# POWERMANAGE.net
KiCad netlist of a schematic drawn in Altium Designer
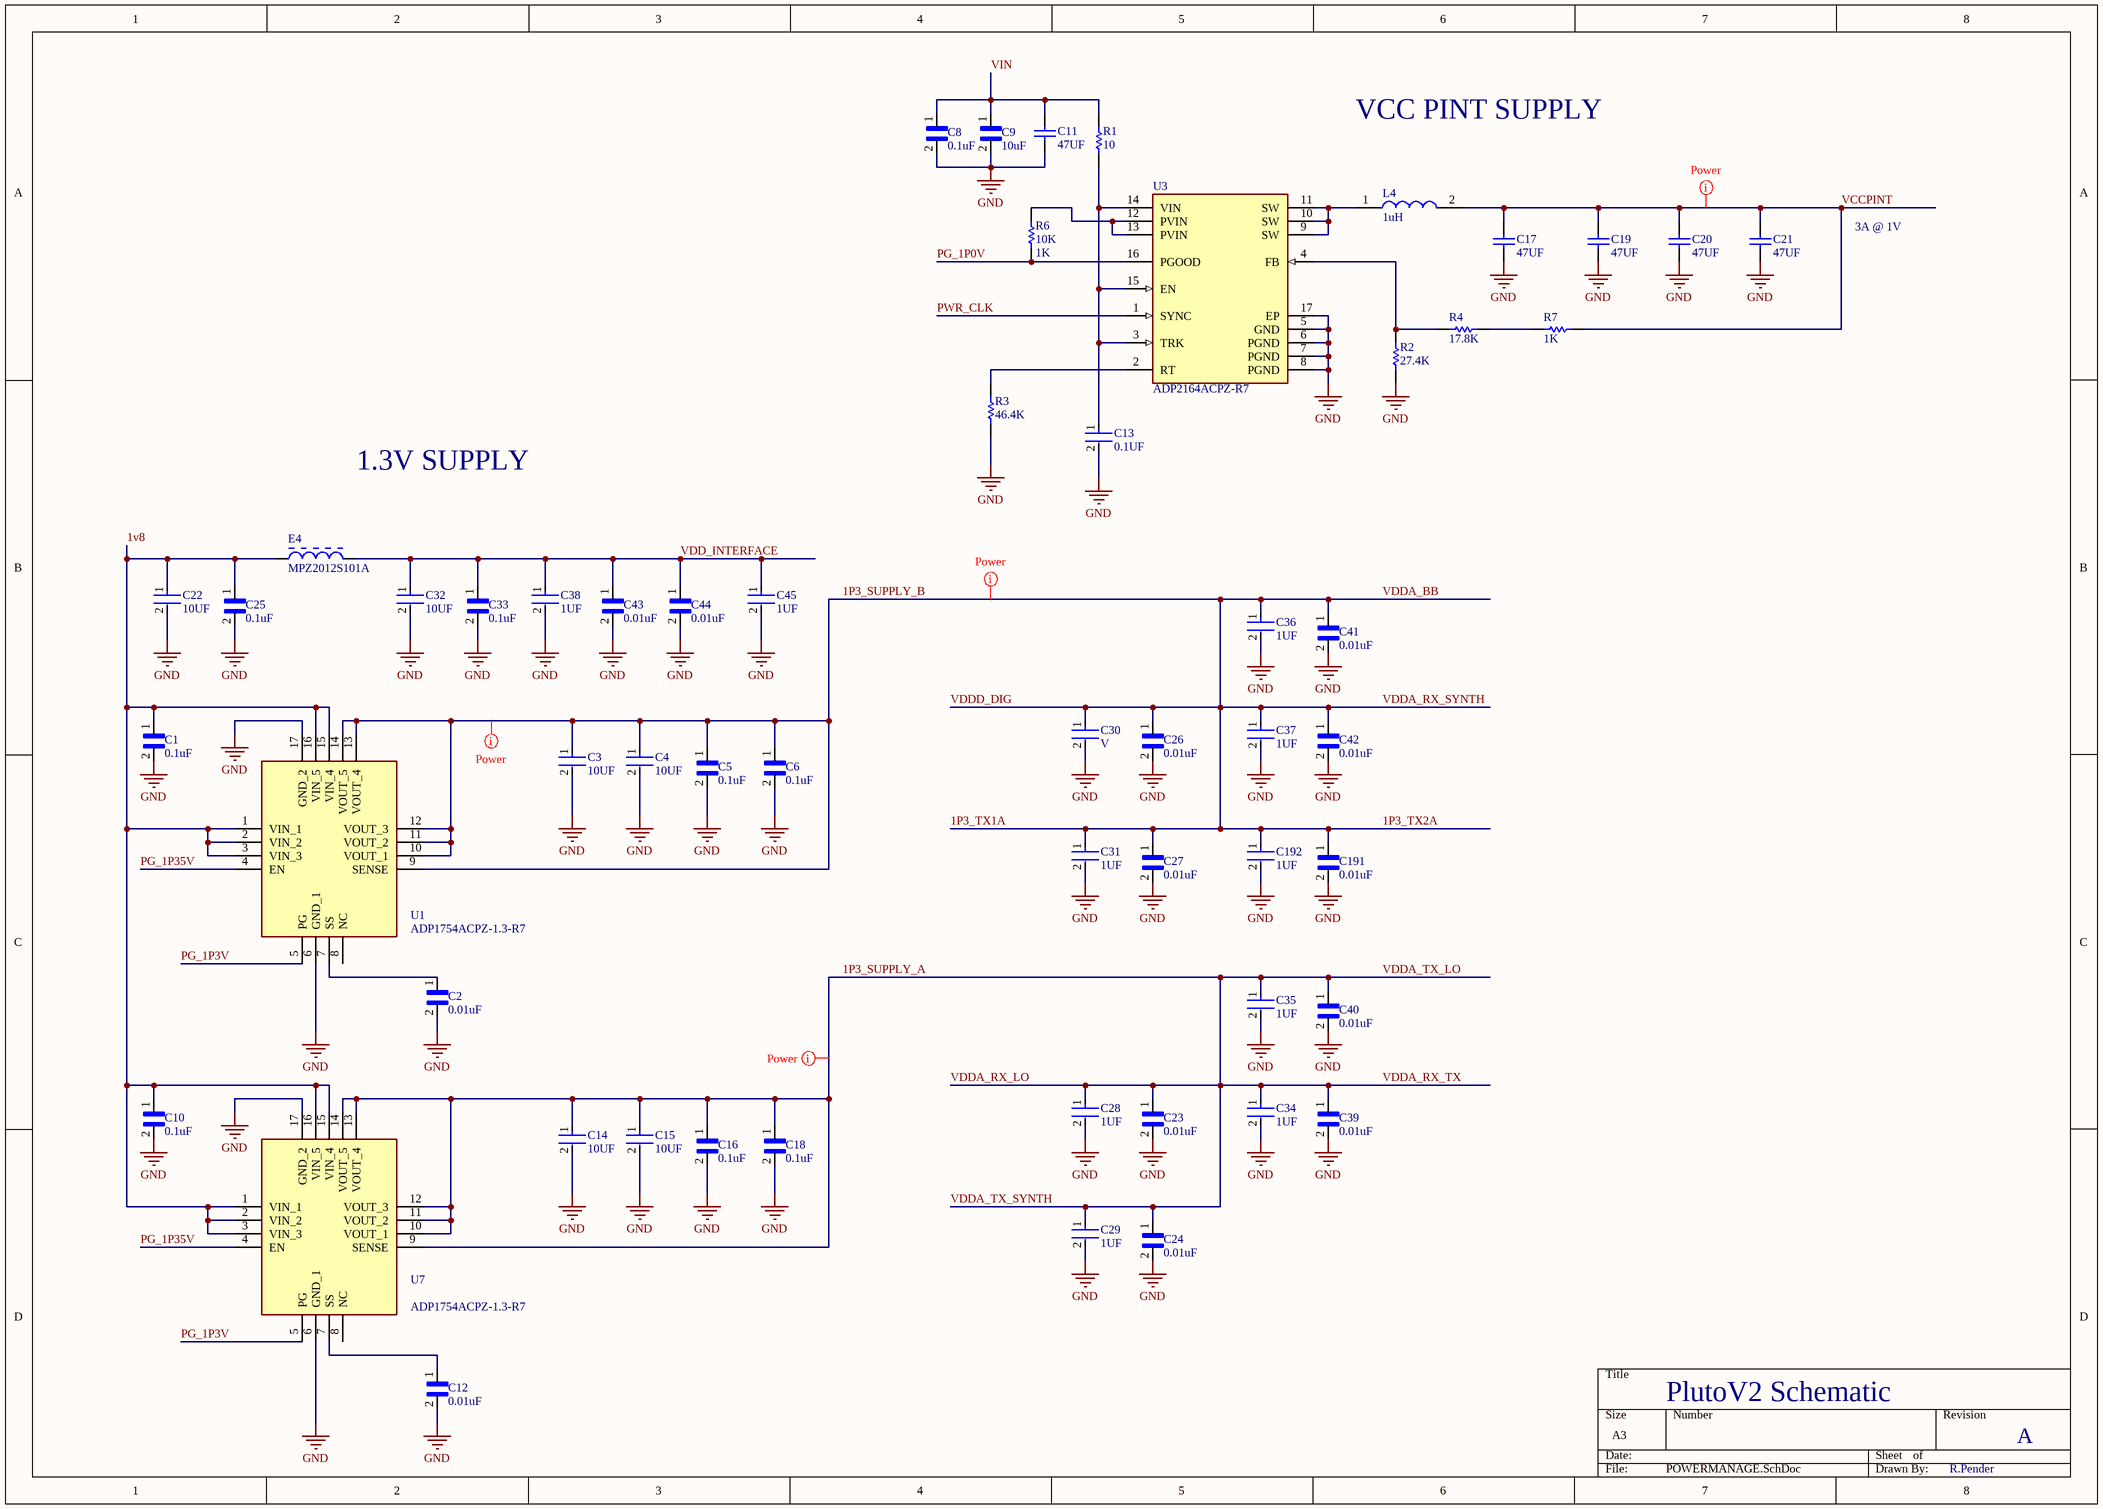
[diagram p0: POWERMANAGE.SchDoc]

(export (version "E")
  (design (tool "Eeschema 10.0.6"))
  (components
    (comp (ref "C1")
      (value "0.1uF")
      (footprint "CAPC0603X33N")
      (description "CAP 0.1UF 16VDC X5R 20% SMD 0201 PAPER TAPE")
      (fields (field (name "MP") "GRM033R61C104ME84D"))
      (libsource (lib "GRM033R61C104ME84D") (part "GRM033R61C104ME84D"))
    )
    (comp (ref "C2")
      (value "0.01uF")
      (footprint "CAPC0603X33N")
      (description "SMD Capacitor X7R(EIA) with Capacitance: 10000pF Tol. 10%. Rated Voltage: 10Vdc")
      (fields (field (name "MP") "GRM033R71A103KA01D") (field (name "MF") "Murata"))
      (libsource (lib "GRM033R71A103KA01D") (part "GRM033R71A103KA01D"))
    )
    (comp (ref "C3")
      (value "10UF")
      (footprint "FP-GRM188-0_1-e0_2_0_55-IPC_A")
      (description "Chip Multilayer Ceramic Capacitors for General Purpose, 0603, 10uF, X5R, 15%, 20%, 6.3V")
      (fields (field (name "VOLTAGE") "6.3V") (field (name "TOLERANCE") "20%"))
      (libsource (lib "Altium Content Vault") (part "02cd4be3c70576c341d710602a673aa"))
    )
    (comp (ref "C4")
      (value "10UF")
      (footprint "FP-GRM188-0_1-e0_2_0_55-IPC_A")
      (description "Chip Multilayer Ceramic Capacitors for General Purpose, 0603, 10uF, X5R, 15%, 20%, 6.3V")
      (fields (field (name "VOLTAGE") "6.3V") (field (name "TOLERANCE") "20%"))
      (libsource (lib "Altium Content Vault") (part "02cd4be3c70576c341d710602a673aa"))
    )
    (comp (ref "C5")
      (value "0.1uF")
      (footprint "CAPC0603X33N")
      (description "CAP 0.1UF 16VDC X5R 20% SMD 0201 PAPER TAPE")
      (fields (field (name "MP") "GRM033R61C104ME84D"))
      (libsource (lib "GRM033R61C104ME84D") (part "GRM033R61C104ME84D"))
    )
    (comp (ref "C6")
      (value "0.1uF")
      (footprint "CAPC0603X33N")
      (description "CAP 0.1UF 16VDC X5R 20% SMD 0201 PAPER TAPE")
      (fields (field (name "MP") "GRM033R61C104ME84D"))
      (libsource (lib "GRM033R61C104ME84D") (part "GRM033R61C104ME84D"))
    )
    (comp (ref "C8")
      (value "0.1uF")
      (footprint "CAPC0603X33N")
      (description "CAP 0.1UF 16VDC X5R 20% SMD 0201 PAPER TAPE")
      (fields (field (name "MP") "GRM033R61C104ME84D"))
      (libsource (lib "GRM033R61C104ME84D") (part "GRM033R61C104ME84D"))
    )
    (comp (ref "C9")
      (value "10uF")
      (footprint "CAPC0603X33N")
      (description "SMD Capacitor X7R(EIA) with Capacitance: 10000pF Tol. 10%. Rated Voltage: 10Vdc")
      (fields (field (name "MP") "GRM033R71A103KA01D") (field (name "MF") "Murata"))
      (libsource (lib "GRM033R71A103KA01D") (part "GRM033R71A103KA01D"))
    )
    (comp (ref "C10")
      (value "0.1uF")
      (footprint "CAPC0603X33N")
      (description "CAP 0.1UF 16VDC X5R 20% SMD 0201 PAPER TAPE")
      (fields (field (name "MP") "GRM033R61C104ME84D"))
      (libsource (lib "GRM033R61C104ME84D") (part "GRM033R61C104ME84D"))
    )
    (comp (ref "C11")
      (value "47UF")
      (footprint "TAYO-JMK212BBJ476MG-T_L")
      (fields
        (field (name "MANUFACTURER") "Taiyo Yuden")
        (field (name "TOLERANCE") "±20%")
        (field (name "PCN PART NUMBER") "X5R,X7RDielectrics23/Jan/2008")
      )
      (libsource (lib "Altium Content Vault") (part "CAP-NP-2"))
    )
    (comp (ref "C12")
      (value "0.01uF")
      (footprint "CAPC0603X33N")
      (description "SMD Capacitor X7R(EIA) with Capacitance: 10000pF Tol. 10%. Rated Voltage: 10Vdc")
      (fields (field (name "MP") "GRM033R71A103KA01D") (field (name "MF") "Murata"))
      (libsource (lib "GRM033R71A103KA01D") (part "GRM033R71A103KA01D"))
    )
    (comp (ref "C13")
      (value "0.1UF")
      (footprint "FP-GRM188-0_15-MFG")
      (description "Chip Multilayer Ceramic Capacitors for General Purpose, 0603, 10uF, X5R, 15%, 20%, 10V")
      (fields (field (name "TOLERANCE") "20%"))
      (libsource (lib "Altium Content Vault") (part "02cd4be3c70576c341d710602a673aa"))
    )
    (comp (ref "C14")
      (value "10UF")
      (footprint "FP-GRM188-0_1-e0_2_0_55-IPC_A")
      (description "Chip Multilayer Ceramic Capacitors for General Purpose, 0603, 10uF, X5R, 15%, 20%, 6.3V")
      (fields (field (name "VOLTAGE") "6.3V") (field (name "TOLERANCE") "20%"))
      (libsource (lib "Altium Content Vault") (part "02cd4be3c70576c341d710602a673aa"))
    )
    (comp (ref "C15")
      (value "10UF")
      (footprint "FP-GRM188-0_1-e0_2_0_55-IPC_A")
      (description "Chip Multilayer Ceramic Capacitors for General Purpose, 0603, 10uF, X5R, 15%, 20%, 6.3V")
      (fields (field (name "VOLTAGE") "6.3V") (field (name "TOLERANCE") "20%"))
      (libsource (lib "Altium Content Vault") (part "02cd4be3c70576c341d710602a673aa"))
    )
    (comp (ref "C16")
      (value "0.1uF")
      (footprint "CAPC0603X33N")
      (description "CAP 0.1UF 16VDC X5R 20% SMD 0201 PAPER TAPE")
      (fields (field (name "MP") "GRM033R61C104ME84D"))
      (libsource (lib "GRM033R61C104ME84D") (part "GRM033R61C104ME84D"))
    )
    (comp (ref "C17")
      (value "47UF")
      (footprint "TAYO-JMK212BBJ476MG-T_L")
      (fields
        (field (name "MANUFACTURER") "Taiyo Yuden")
        (field (name "TOLERANCE") "±20%")
        (field (name "PCN PART NUMBER") "X5R,X7RDielectrics23/Jan/2008")
      )
      (libsource (lib "Altium Content Vault") (part "CAP-NP-2"))
    )
    (comp (ref "C18")
      (value "0.1uF")
      (footprint "CAPC0603X33N")
      (description "CAP 0.1UF 16VDC X5R 20% SMD 0201 PAPER TAPE")
      (fields (field (name "MP") "GRM033R61C104ME84D"))
      (libsource (lib "GRM033R61C104ME84D") (part "GRM033R61C104ME84D"))
    )
    (comp (ref "C19")
      (value "47UF")
      (footprint "TAYO-JMK212BBJ476MG-T_L")
      (fields
        (field (name "MANUFACTURER") "Taiyo Yuden")
        (field (name "TOLERANCE") "±20%")
        (field (name "PCN PART NUMBER") "X5R,X7RDielectrics23/Jan/2008")
      )
      (libsource (lib "Altium Content Vault") (part "CAP-NP-2"))
    )
    (comp (ref "C20")
      (value "47UF")
      (footprint "TAYO-JMK212BBJ476MG-T_L")
      (fields
        (field (name "MANUFACTURER") "Taiyo Yuden")
        (field (name "TOLERANCE") "±20%")
        (field (name "PCN PART NUMBER") "X5R,X7RDielectrics23/Jan/2008")
      )
      (libsource (lib "Altium Content Vault") (part "CAP-NP-2"))
    )
    (comp (ref "C21")
      (value "47UF")
      (footprint "TAYO-JMK212BBJ476MG-T_L")
      (fields
        (field (name "MANUFACTURER") "Taiyo Yuden")
        (field (name "TOLERANCE") "±20%")
        (field (name "PCN PART NUMBER") "X5R,X7RDielectrics23/Jan/2008")
      )
      (libsource (lib "Altium Content Vault") (part "CAP-NP-2"))
    )
    (comp (ref "C22")
      (value "10UF")
      (footprint "FP-GRM188-0_1-e0_2_0_55-IPC_A")
      (description "Chip Multilayer Ceramic Capacitors for General Purpose, 0603, 10uF, X5R, 15%, 20%, 6.3V")
      (fields (field (name "VOLTAGE") "6.3V") (field (name "TOLERANCE") "20%"))
      (libsource (lib "Altium Content Vault") (part "02cd4be3c70576c341d710602a673aa"))
    )
    (comp (ref "C23")
      (value "0.01uF")
      (footprint "CAPC0603X33N")
      (description "SMD Capacitor X7R(EIA) with Capacitance: 10000pF Tol. 10%. Rated Voltage: 10Vdc")
      (fields (field (name "MP") "GRM033R71A103KA01D") (field (name "MF") "Murata"))
      (libsource (lib "GRM033R71A103KA01D") (part "GRM033R71A103KA01D"))
    )
    (comp (ref "C24")
      (value "0.01uF")
      (footprint "CAPC0603X33N")
      (description "SMD Capacitor X7R(EIA) with Capacitance: 10000pF Tol. 10%. Rated Voltage: 10Vdc")
      (fields (field (name "MP") "GRM033R71A103KA01D") (field (name "MF") "Murata"))
      (libsource (lib "GRM033R71A103KA01D") (part "GRM033R71A103KA01D"))
    )
    (comp (ref "C25")
      (value "0.1uF")
      (footprint "CAPC0603X33N")
      (description "CAP 0.1UF 16VDC X5R 20% SMD 0201 PAPER TAPE")
      (fields (field (name "MP") "GRM033R61C104ME84D"))
      (libsource (lib "GRM033R61C104ME84D") (part "GRM033R61C104ME84D"))
    )
    (comp (ref "C26")
      (value "0.01uF")
      (footprint "CAPC0603X33N")
      (description "SMD Capacitor X7R(EIA) with Capacitance: 10000pF Tol. 10%. Rated Voltage: 10Vdc")
      (fields (field (name "MP") "GRM033R71A103KA01D") (field (name "MF") "Murata"))
      (libsource (lib "GRM033R71A103KA01D") (part "GRM033R71A103KA01D"))
    )
    (comp (ref "C27")
      (value "0.01uF")
      (footprint "CAPC0603X33N")
      (description "SMD Capacitor X7R(EIA) with Capacitance: 10000pF Tol. 10%. Rated Voltage: 10Vdc")
      (fields (field (name "MP") "GRM033R71A103KA01D") (field (name "MF") "Murata"))
      (libsource (lib "GRM033R71A103KA01D") (part "GRM033R71A103KA01D"))
    )
    (comp (ref "C28")
      (value "1UF")
      (footprint "FP-0402-L_1_0_0_05-W_0_5-IPC_A")
      (description "None")
      (fields (field (name "TOLERANCE") "10%"))
      (libsource (lib "Altium Content Vault") (part "b4654b650e69147ec39a6b967a45e02"))
    )
    (comp (ref "C29")
      (value "1UF")
      (footprint "FP-0402-L_1_0_0_05-W_0_5-IPC_A")
      (description "None")
      (fields (field (name "TOLERANCE") "10%"))
      (libsource (lib "Altium Content Vault") (part "b4654b650e69147ec39a6b967a45e02"))
    )
    (comp (ref "C30")
      (value "V")
      (footprint "FP-0402-L_1_0_0_05-W_0_5-IPC_A")
      (description "None")
      (fields (field (name "TOLERANCE") "10%"))
      (libsource (lib "Altium Content Vault") (part "b4654b650e69147ec39a6b967a45e02"))
    )
    (comp (ref "C31")
      (value "1UF")
      (footprint "FP-0402-L_1_0_0_05-W_0_5-IPC_A")
      (description "None")
      (fields (field (name "TOLERANCE") "10%"))
      (libsource (lib "Altium Content Vault") (part "b4654b650e69147ec39a6b967a45e02"))
    )
    (comp (ref "C32")
      (value "10UF")
      (footprint "FP-GRM188-0_1-e0_2_0_55-IPC_A")
      (description "Chip Multilayer Ceramic Capacitors for General Purpose, 0603, 10uF, X5R, 15%, 20%, 6.3V")
      (fields (field (name "VOLTAGE") "6.3V") (field (name "TOLERANCE") "20%"))
      (libsource (lib "Altium Content Vault") (part "02cd4be3c70576c341d710602a673aa"))
    )
    (comp (ref "C33")
      (value "0.1uF")
      (footprint "CAPC0603X33N")
      (description "CAP 0.1UF 16VDC X5R 20% SMD 0201 PAPER TAPE")
      (fields (field (name "MP") "GRM033R61C104ME84D"))
      (libsource (lib "GRM033R61C104ME84D") (part "GRM033R61C104ME84D"))
    )
    (comp (ref "C34")
      (value "1UF")
      (footprint "FP-0402-L_1_0_0_05-W_0_5-IPC_A")
      (description "None")
      (fields (field (name "TOLERANCE") "10%"))
      (libsource (lib "Altium Content Vault") (part "b4654b650e69147ec39a6b967a45e02"))
    )
    (comp (ref "C35")
      (value "1UF")
      (footprint "FP-0402-L_1_0_0_05-W_0_5-IPC_A")
      (description "None")
      (fields (field (name "TOLERANCE") "10%"))
      (libsource (lib "Altium Content Vault") (part "b4654b650e69147ec39a6b967a45e02"))
    )
    (comp (ref "C36")
      (value "1UF")
      (footprint "FP-0402-L_1_0_0_05-W_0_5-IPC_A")
      (description "None")
      (fields (field (name "TOLERANCE") "10%"))
      (libsource (lib "Altium Content Vault") (part "b4654b650e69147ec39a6b967a45e02"))
    )
    (comp (ref "C37")
      (value "1UF")
      (footprint "FP-0402-L_1_0_0_05-W_0_5-IPC_A")
      (description "None")
      (fields (field (name "TOLERANCE") "10%"))
      (libsource (lib "Altium Content Vault") (part "b4654b650e69147ec39a6b967a45e02"))
    )
    (comp (ref "C38")
      (value "1UF")
      (footprint "FP-0402-L_1_0_0_05-W_0_5-IPC_A")
      (description "None")
      (fields (field (name "TOLERANCE") "10%"))
      (libsource (lib "Altium Content Vault") (part "b4654b650e69147ec39a6b967a45e02"))
    )
    (comp (ref "C39")
      (value "0.01uF")
      (footprint "CAPC0603X33N")
      (description "SMD Capacitor X7R(EIA) with Capacitance: 10000pF Tol. 10%. Rated Voltage: 10Vdc")
      (fields (field (name "MP") "GRM033R71A103KA01D") (field (name "MF") "Murata"))
      (libsource (lib "GRM033R71A103KA01D") (part "GRM033R71A103KA01D"))
    )
    (comp (ref "C40")
      (value "0.01uF")
      (footprint "CAPC0603X33N")
      (description "SMD Capacitor X7R(EIA) with Capacitance: 10000pF Tol. 10%. Rated Voltage: 10Vdc")
      (fields (field (name "MP") "GRM033R71A103KA01D") (field (name "MF") "Murata"))
      (libsource (lib "GRM033R71A103KA01D") (part "GRM033R71A103KA01D"))
    )
    (comp (ref "C41")
      (value "0.01uF")
      (footprint "CAPC0603X33N")
      (description "SMD Capacitor X7R(EIA) with Capacitance: 10000pF Tol. 10%. Rated Voltage: 10Vdc")
      (fields (field (name "MP") "GRM033R71A103KA01D") (field (name "MF") "Murata"))
      (libsource (lib "GRM033R71A103KA01D") (part "GRM033R71A103KA01D"))
    )
    (comp (ref "C42")
      (value "0.01uF")
      (footprint "CAPC0603X33N")
      (description "SMD Capacitor X7R(EIA) with Capacitance: 10000pF Tol. 10%. Rated Voltage: 10Vdc")
      (fields (field (name "MP") "GRM033R71A103KA01D") (field (name "MF") "Murata"))
      (libsource (lib "GRM033R71A103KA01D") (part "GRM033R71A103KA01D"))
    )
    (comp (ref "C43")
      (value "0.01uF")
      (footprint "CAPC0603X33N")
      (description "SMD Capacitor X7R(EIA) with Capacitance: 10000pF Tol. 10%. Rated Voltage: 10Vdc")
      (fields (field (name "MP") "GRM033R71A103KA01D") (field (name "MF") "Murata"))
      (libsource (lib "GRM033R71A103KA01D") (part "GRM033R71A103KA01D"))
    )
    (comp (ref "C44")
      (value "0.01uF")
      (footprint "CAPC0603X33N")
      (description "SMD Capacitor X7R(EIA) with Capacitance: 10000pF Tol. 10%. Rated Voltage: 10Vdc")
      (fields (field (name "MP") "GRM033R71A103KA01D") (field (name "MF") "Murata"))
      (libsource (lib "GRM033R71A103KA01D") (part "GRM033R71A103KA01D"))
    )
    (comp (ref "C45")
      (value "1UF")
      (footprint "FP-0402-L_1_0_0_05-W_0_5-IPC_A")
      (description "None")
      (fields (field (name "TOLERANCE") "10%"))
      (libsource (lib "Altium Content Vault") (part "b4654b650e69147ec39a6b967a45e02"))
    )
    (comp (ref "C191")
      (value "0.01uF")
      (footprint "CAPC0603X33N")
      (description "SMD Capacitor X7R(EIA) with Capacitance: 10000pF Tol. 10%. Rated Voltage: 10Vdc")
      (fields (field (name "MP") "GRM033R71A103KA01D") (field (name "MF") "Murata"))
      (libsource (lib "GRM033R71A103KA01D") (part "GRM033R71A103KA01D"))
    )
    (comp (ref "C192")
      (value "1UF")
      (footprint "FP-0402-L_1_0_0_05-W_0_5-IPC_A")
      (description "None")
      (fields (field (name "TOLERANCE") "10%"))
      (libsource (lib "Altium Content Vault") (part "b4654b650e69147ec39a6b967a45e02"))
    )
    (comp (ref "E4")
      (value "MPZ2012S101A")
      (footprint "TDK-MPZ2012S101A-2_V")
      (fields (field (name "TOLERANCE") "25%") (field (name "MANUFACTURER") "TDK"))
      (libsource (lib "Altium Content Vault") (part "BEAD-2"))
    )
    (comp (ref "L4")
      (value "1uH")
      (footprint "SamacSys:XFL4020102MEB")
      (description "Inductor")
      (fields (field (name "MANUFACTURER_PART_NUMBER") "XFL4020-102MEB"))
      (libsource (lib "SamacSys") (part "XFL4020-102MEB"))
    )
    (comp (ref "R1")
      (value "10")
      (footprint "RESC0603X26X15LL03T05")
      (fields (field (name "MANUFACTURER") "Panasonic") (field (name "PART NUMBER") "ERJ1GNF10R0C"))
      (libsource (lib "Altium Content Vault") (part "RES"))
    )
    (comp (ref "R2")
      (value "27.4K")
      (footprint "2-0402")
      (fields (field (name "PUBLISHER") "Altium Limited"))
      (libsource (lib "Panasonic Resistor") (part "ERJ2RK"))
    )
    (comp (ref "R3")
      (value "46.4K")
      (footprint "1-0201")
      (description "Thick Film Chip Resistor, 10 Ohm to 1M Ohm Range, 5% Tolerance, 0201 Size, 0.05 W")
      (fields (field (name "PUBLISHER") "Altium Limited"))
      (libsource (lib "Panasonic Resistor") (part "ERJ1GE"))
    )
    (comp (ref "R4")
      (value "17.8K")
      (footprint "2-0402")
      (fields (field (name "PUBLISHER") "Altium Limited"))
      (libsource (lib "Panasonic Resistor") (part "ERJ2RK"))
    )
    (comp (ref "R6")
      (value "10K")
      (footprint "AXIAL-0.3")
      (description "Resistor")
      (fields (field (name "ALTIUM_VALUE") "1K") (field (name "PUBLISHER") "Altium Limited"))
      (libsource (lib "Miscellaneous Devices") (part "Res1"))
    )
    (comp (ref "R7")
      (value "1K")
      (footprint "2-0402")
      (fields (field (name "PUBLISHER") "Altium Limited"))
      (libsource (lib "Panasonic Resistor") (part "ERJ2RK"))
    )
    (comp (ref "U1")
      (value "ADP1754ACPZ-1.3-R7")
      (footprint "SamacSys:QFN65P400X400X80-17N-D")
      (description "Integrated Circuit")
      (libsource (lib "SamacSys") (part "ADP1754ACPZ-1.3-R7"))
    )
    (comp (ref "U3")
      (value "ADP2164ACPZ-R7")
      (footprint "FP-CP-16-26-IPC_C")
      (description "IC REG BUCK ADJ 4A 16LFCSP")
      (fields
        (field (name "MANUFACTURER") "Analog Devices")
        (field (name "OCTOPART") "https://octopart.com/adp2164acpz-r7-analog+devices-21054168")
      )
      (libsource (lib "Altium Content Vault") (part "77e3d03b05ecb97249e3a8385dd6fb0"))
    )
    (comp (ref "U7")
      (value "ADP1754ACPZ-1.3-R7")
      (footprint "SamacSys:QFN65P400X400X80-17N-D")
      (description "Integrated Circuit")
      (libsource (lib "SamacSys") (part "ADP1754ACPZ-1.3-R7"))
    )
  )
  (nets
    (net (code "1") (name "/1P3_SUPPLY_A") (class "Default")
      (node (ref "C14") (pin "1") (pinfunction "1_1") (pintype "passive"))
      (node (ref "C15") (pin "1") (pinfunction "1_1") (pintype "passive"))
      (node (ref "C16") (pin "1") (pinfunction "1_1") (pintype "passive"))
      (node (ref "C18") (pin "1") (pinfunction "1_1") (pintype "passive"))
      (node (ref "C23") (pin "1") (pinfunction "1_1") (pintype "passive"))
      (node (ref "C24") (pin "1") (pinfunction "1_1") (pintype "passive"))
      (node (ref "C28") (pin "1") (pinfunction "1_1") (pintype "passive"))
      (node (ref "C29") (pin "1") (pinfunction "1_1") (pintype "passive"))
      (node (ref "C34") (pin "1") (pinfunction "1_1") (pintype "passive"))
      (node (ref "C35") (pin "1") (pinfunction "1_1") (pintype "passive"))
      (node (ref "C39") (pin "1") (pinfunction "1_1") (pintype "passive"))
      (node (ref "C40") (pin "1") (pinfunction "1_1") (pintype "passive"))
      (node (ref "U7") (pin "10") (pinfunction "VOUT_1_10") (pintype "passive"))
      (node (ref "U7") (pin "11") (pinfunction "VOUT_2_11") (pintype "passive"))
      (node (ref "U7") (pin "12") (pinfunction "VOUT_3_12") (pintype "passive"))
      (node (ref "U7") (pin "13") (pinfunction "VOUT_4_13") (pintype "passive"))
      (node (ref "U7") (pin "14") (pinfunction "VOUT_5_14") (pintype "passive"))
      (node (ref "U7") (pin "9") (pinfunction "SENSE_9") (pintype "passive"))
    )
    (net (code "2") (name "/1P3_SUPPLY_B") (class "Default")
      (node (ref "C191") (pin "1") (pinfunction "1_1") (pintype "passive"))
      (node (ref "C192") (pin "1") (pinfunction "1_1") (pintype "passive"))
      (node (ref "C26") (pin "1") (pinfunction "1_1") (pintype "passive"))
      (node (ref "C27") (pin "1") (pinfunction "1_1") (pintype "passive"))
      (node (ref "C3") (pin "1") (pinfunction "1_1") (pintype "passive"))
      (node (ref "C30") (pin "1") (pinfunction "1_1") (pintype "passive"))
      (node (ref "C31") (pin "1") (pinfunction "1_1") (pintype "passive"))
      (node (ref "C36") (pin "1") (pinfunction "1_1") (pintype "passive"))
      (node (ref "C37") (pin "1") (pinfunction "1_1") (pintype "passive"))
      (node (ref "C4") (pin "1") (pinfunction "1_1") (pintype "passive"))
      (node (ref "C41") (pin "1") (pinfunction "1_1") (pintype "passive"))
      (node (ref "C42") (pin "1") (pinfunction "1_1") (pintype "passive"))
      (node (ref "C5") (pin "1") (pinfunction "1_1") (pintype "passive"))
      (node (ref "C6") (pin "1") (pinfunction "1_1") (pintype "passive"))
      (node (ref "U1") (pin "10") (pinfunction "VOUT_1_10") (pintype "passive"))
      (node (ref "U1") (pin "11") (pinfunction "VOUT_2_11") (pintype "passive"))
      (node (ref "U1") (pin "12") (pinfunction "VOUT_3_12") (pintype "passive"))
      (node (ref "U1") (pin "13") (pinfunction "VOUT_4_13") (pintype "passive"))
      (node (ref "U1") (pin "14") (pinfunction "VOUT_5_14") (pintype "passive"))
      (node (ref "U1") (pin "9") (pinfunction "SENSE_9") (pintype "passive"))
    )
    (net (code "3") (name "/1v8") (class "Default")
      (node (ref "C1") (pin "1") (pinfunction "1_1") (pintype "passive"))
      (node (ref "C10") (pin "1") (pinfunction "1_1") (pintype "passive"))
      (node (ref "C22") (pin "1") (pinfunction "1_1") (pintype "passive"))
      (node (ref "C25") (pin "1") (pinfunction "1_1") (pintype "passive"))
      (node (ref "E4") (pin "1") (pinfunction "1_1") (pintype "passive"))
      (node (ref "U1") (pin "1") (pinfunction "VIN_1_1") (pintype "passive"))
      (node (ref "U1") (pin "15") (pinfunction "VIN_4_15") (pintype "passive"))
      (node (ref "U1") (pin "16") (pinfunction "VIN_5_16") (pintype "passive"))
      (node (ref "U1") (pin "2") (pinfunction "VIN_2_2") (pintype "passive"))
      (node (ref "U1") (pin "3") (pinfunction "VIN_3_3") (pintype "passive"))
      (node (ref "U7") (pin "1") (pinfunction "VIN_1_1") (pintype "passive"))
      (node (ref "U7") (pin "15") (pinfunction "VIN_4_15") (pintype "passive"))
      (node (ref "U7") (pin "16") (pinfunction "VIN_5_16") (pintype "passive"))
      (node (ref "U7") (pin "2") (pinfunction "VIN_2_2") (pintype "passive"))
      (node (ref "U7") (pin "3") (pinfunction "VIN_3_3") (pintype "passive"))
    )
    (net (code "4") (name "/PG_1P0V") (class "Default")
      (node (ref "R6") (pin "1") (pinfunction "1_1") (pintype "passive"))
      (node (ref "U3") (pin "16") (pinfunction "PGOOD_16") (pintype "open_collector"))
    )
    (net (code "5") (name "/PG_1P3V") (class "Default")
      (node (ref "U1") (pin "5") (pinfunction "PG_5") (pintype "passive"))
      (node (ref "U7") (pin "5") (pinfunction "PG_5") (pintype "passive"))
    )
    (net (code "6") (name "/PG_1P35V") (class "Default")
      (node (ref "U1") (pin "4") (pinfunction "EN_4") (pintype "passive"))
      (node (ref "U7") (pin "4") (pinfunction "EN_4") (pintype "passive"))
    )
    (net (code "7") (name "/PWR_CLK") (class "Default")
      (node (ref "U3") (pin "1") (pinfunction "SYNC_1") (pintype "input"))
    )
    (net (code "8") (name "/VCCPINT") (class "Default")
      (node (ref "C17") (pin "1") (pinfunction "1_1") (pintype "passive"))
      (node (ref "C19") (pin "1") (pinfunction "1_1") (pintype "passive"))
      (node (ref "C20") (pin "1") (pinfunction "1_1") (pintype "passive"))
      (node (ref "C21") (pin "1") (pinfunction "1_1") (pintype "passive"))
      (node (ref "L4") (pin "2") (pinfunction "2_2") (pintype "passive"))
      (node (ref "R7") (pin "2") (pinfunction "2_2") (pintype "passive"))
    )
    (net (code "9") (name "/VDD_INTERFACE") (class "Default")
      (node (ref "C32") (pin "1") (pinfunction "1_1") (pintype "passive"))
      (node (ref "C33") (pin "1") (pinfunction "1_1") (pintype "passive"))
      (node (ref "C38") (pin "1") (pinfunction "1_1") (pintype "passive"))
      (node (ref "C43") (pin "1") (pinfunction "1_1") (pintype "passive"))
      (node (ref "C44") (pin "1") (pinfunction "1_1") (pintype "passive"))
      (node (ref "C45") (pin "1") (pinfunction "1_1") (pintype "passive"))
      (node (ref "E4") (pin "2") (pinfunction "2_2") (pintype "passive"))
    )
    (net (code "10") (name "/VIN") (class "Default")
      (node (ref "C11") (pin "1") (pinfunction "1_1") (pintype "passive"))
      (node (ref "C8") (pin "1") (pinfunction "1_1") (pintype "passive"))
      (node (ref "C9") (pin "1") (pinfunction "1_1") (pintype "passive"))
      (node (ref "R1") (pin "2") (pinfunction "2_2") (pintype "passive"))
    )
    (net (code "11") (name "GND") (class "Default")
      (node (ref "C1") (pin "2") (pinfunction "2_2") (pintype "passive"))
      (node (ref "C10") (pin "2") (pinfunction "2_2") (pintype "passive"))
      (node (ref "C11") (pin "2") (pinfunction "2_2") (pintype "passive"))
      (node (ref "C12") (pin "2") (pinfunction "2_2") (pintype "passive"))
      (node (ref "C13") (pin "2") (pinfunction "2_2") (pintype "passive"))
      (node (ref "C14") (pin "2") (pinfunction "2_2") (pintype "passive"))
      (node (ref "C15") (pin "2") (pinfunction "2_2") (pintype "passive"))
      (node (ref "C16") (pin "2") (pinfunction "2_2") (pintype "passive"))
      (node (ref "C17") (pin "2") (pinfunction "2_2") (pintype "passive"))
      (node (ref "C18") (pin "2") (pinfunction "2_2") (pintype "passive"))
      (node (ref "C19") (pin "2") (pinfunction "2_2") (pintype "passive"))
      (node (ref "C191") (pin "2") (pinfunction "2_2") (pintype "passive"))
      (node (ref "C192") (pin "2") (pinfunction "2_2") (pintype "passive"))
      (node (ref "C2") (pin "2") (pinfunction "2_2") (pintype "passive"))
      (node (ref "C20") (pin "2") (pinfunction "2_2") (pintype "passive"))
      (node (ref "C21") (pin "2") (pinfunction "2_2") (pintype "passive"))
      (node (ref "C22") (pin "2") (pinfunction "2_2") (pintype "passive"))
      (node (ref "C23") (pin "2") (pinfunction "2_2") (pintype "passive"))
      (node (ref "C24") (pin "2") (pinfunction "2_2") (pintype "passive"))
      (node (ref "C25") (pin "2") (pinfunction "2_2") (pintype "passive"))
      (node (ref "C26") (pin "2") (pinfunction "2_2") (pintype "passive"))
      (node (ref "C27") (pin "2") (pinfunction "2_2") (pintype "passive"))
      (node (ref "C28") (pin "2") (pinfunction "2_2") (pintype "passive"))
      (node (ref "C29") (pin "2") (pinfunction "2_2") (pintype "passive"))
      (node (ref "C3") (pin "2") (pinfunction "2_2") (pintype "passive"))
      (node (ref "C30") (pin "2") (pinfunction "2_2") (pintype "passive"))
      (node (ref "C31") (pin "2") (pinfunction "2_2") (pintype "passive"))
      (node (ref "C32") (pin "2") (pinfunction "2_2") (pintype "passive"))
      (node (ref "C33") (pin "2") (pinfunction "2_2") (pintype "passive"))
      (node (ref "C34") (pin "2") (pinfunction "2_2") (pintype "passive"))
      (node (ref "C35") (pin "2") (pinfunction "2_2") (pintype "passive"))
      (node (ref "C36") (pin "2") (pinfunction "2_2") (pintype "passive"))
      (node (ref "C37") (pin "2") (pinfunction "2_2") (pintype "passive"))
      (node (ref "C38") (pin "2") (pinfunction "2_2") (pintype "passive"))
      (node (ref "C39") (pin "2") (pinfunction "2_2") (pintype "passive"))
      (node (ref "C4") (pin "2") (pinfunction "2_2") (pintype "passive"))
      (node (ref "C40") (pin "2") (pinfunction "2_2") (pintype "passive"))
      (node (ref "C41") (pin "2") (pinfunction "2_2") (pintype "passive"))
      (node (ref "C42") (pin "2") (pinfunction "2_2") (pintype "passive"))
      (node (ref "C43") (pin "2") (pinfunction "2_2") (pintype "passive"))
      (node (ref "C44") (pin "2") (pinfunction "2_2") (pintype "passive"))
      (node (ref "C45") (pin "2") (pinfunction "2_2") (pintype "passive"))
      (node (ref "C5") (pin "2") (pinfunction "2_2") (pintype "passive"))
      (node (ref "C6") (pin "2") (pinfunction "2_2") (pintype "passive"))
      (node (ref "C8") (pin "2") (pinfunction "2_2") (pintype "passive"))
      (node (ref "C9") (pin "2") (pinfunction "2_2") (pintype "passive"))
      (node (ref "R2") (pin "2") (pinfunction "2_2") (pintype "passive"))
      (node (ref "R3") (pin "2") (pinfunction "2_2") (pintype "passive"))
      (node (ref "U1") (pin "17") (pinfunction "GND_2_17") (pintype "passive"))
      (node (ref "U1") (pin "6") (pinfunction "GND_1_6") (pintype "passive"))
      (node (ref "U3") (pin "17") (pinfunction "EP_17") (pintype "power_in"))
      (node (ref "U3") (pin "5") (pinfunction "GND_5") (pintype "power_in"))
      (node (ref "U3") (pin "6") (pinfunction "PGND_6") (pintype "power_in"))
      (node (ref "U3") (pin "7") (pinfunction "PGND_7") (pintype "power_in"))
      (node (ref "U3") (pin "8") (pinfunction "PGND_8") (pintype "power_in"))
      (node (ref "U7") (pin "17") (pinfunction "GND_2_17") (pintype "passive"))
      (node (ref "U7") (pin "6") (pinfunction "GND_1_6") (pintype "passive"))
    )
    (net (code "12") (name "Net-(L4-Pad1)") (class "Default")
      (node (ref "L4") (pin "1") (pinfunction "1_1") (pintype "passive"))
      (node (ref "U3") (pin "10") (pinfunction "SW_10") (pintype "power_in"))
      (node (ref "U3") (pin "11") (pinfunction "SW_11") (pintype "power_in"))
      (node (ref "U3") (pin "9") (pinfunction "SW_9") (pintype "power_in"))
    )
    (net (code "13") (name "Net-(R4-Pad2)") (class "Default")
      (node (ref "R4") (pin "2") (pinfunction "2_2") (pintype "passive"))
      (node (ref "R7") (pin "1") (pinfunction "1_1") (pintype "passive"))
    )
    (net (code "14") (name "Net-(R6-Pad2)") (class "Default")
      (node (ref "R6") (pin "2") (pinfunction "2_2") (pintype "passive"))
      (node (ref "U3") (pin "12") (pinfunction "PVIN_12") (pintype "power_in"))
      (node (ref "U3") (pin "13") (pinfunction "PVIN_13") (pintype "power_in"))
    )
    (net (code "15") (name "Net-(U1-SS)") (class "Default")
      (node (ref "C2") (pin "1") (pinfunction "1_1") (pintype "passive"))
      (node (ref "U1") (pin "7") (pinfunction "SS_7") (pintype "passive"))
    )
    (net (code "16") (name "Net-(U3-EN)") (class "Default")
      (node (ref "C13") (pin "1") (pinfunction "1_1") (pintype "passive"))
      (node (ref "R1") (pin "1") (pinfunction "1_1") (pintype "passive"))
      (node (ref "U3") (pin "14") (pinfunction "VIN_14") (pintype "power_in"))
      (node (ref "U3") (pin "15") (pinfunction "EN_15") (pintype "input"))
      (node (ref "U3") (pin "3") (pinfunction "TRK_3") (pintype "input"))
    )
    (net (code "17") (name "Net-(U3-FB)") (class "Default")
      (node (ref "R2") (pin "1") (pinfunction "1_1") (pintype "passive"))
      (node (ref "R4") (pin "1") (pinfunction "1_1") (pintype "passive"))
      (node (ref "U3") (pin "4") (pinfunction "FB_4") (pintype "input"))
    )
    (net (code "18") (name "Net-(U3-RT)") (class "Default")
      (node (ref "R3") (pin "1") (pinfunction "1_1") (pintype "passive"))
      (node (ref "U3") (pin "2") (pinfunction "RT_2") (pintype "passive"))
    )
    (net (code "19") (name "Net-(U7-SS)") (class "Default")
      (node (ref "C12") (pin "1") (pinfunction "1_1") (pintype "passive"))
      (node (ref "U7") (pin "7") (pinfunction "SS_7") (pintype "passive"))
    )
    (net (code "20") (name "unconnected-(U1-NC-Pad8)") (class "Default")
      (node (ref "U1") (pin "8") (pinfunction "NC_8") (pintype "passive"))
    )
    (net (code "21") (name "unconnected-(U7-NC-Pad8)") (class "Default")
      (node (ref "U7") (pin "8") (pinfunction "NC_8") (pintype "passive"))
    )
  )
)
